# ConnS2.net
KiCad netlist of a schematic drawn in Altium Designer
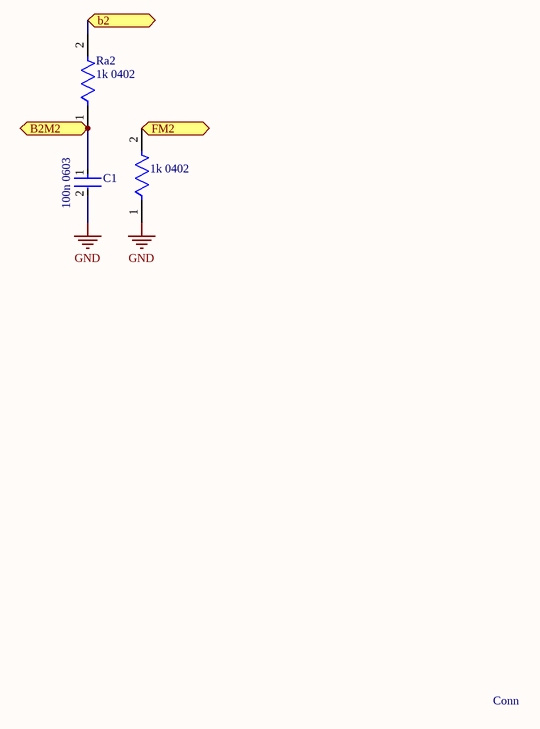
[diagram p0: ConnS2.SchDoc]

(export (version "E")
  (design (tool "Eeschema 10.0.6"))
  (components
    (comp (ref "C1")
      (value "100n 0603")
      (footprint "FP-C0603C-CF-MFG")
      (fields
        (field (name "MANUFACTURER PART NUMBER") "C0603C104K4RACTU")
        (field (name "OCTOPART") "https://octopart.com/c0603c104k4ractu-kemet-93067")
        (field (name "MANUFACTURER") "KEMET")
      )
      (libsource (lib "Altium Content Vault") (part "b4654b650e69147ec39a6b967a45e02"))
    )
    (comp (ref "Ra2")
      (value "1k 0402")
      (footprint "FP-CR0402-IPC_C")
      (description "Thick Film Chip Resistors 0402 1kΩ 0.0625W 1% 100ppm/°C")
      (fields (field (name "TOLERANCE") "1%"))
      (libsource (lib "Altium Content Vault") (part "1029c3af85768c4190bb7ad29bc67b5"))
    )
    (comp (ref "Rb2")
      (value "1k 0402")
      (footprint "FP-CR0402-IPC_C")
      (description "Thick Film Chip Resistors 0402 1kΩ 0.0625W 1% 100ppm/°C")
      (fields (field (name "TOLERANCE") "1%"))
      (libsource (lib "Altium Content Vault") (part "1029c3af85768c4190bb7ad29bc67b5"))
    )
  )
  (nets
    (net (code "1") (name "/B2M2") (class "Default")
      (node (ref "C1") (pin "1") (pinfunction "1_1") (pintype "passive"))
      (node (ref "Ra2") (pin "1") (pinfunction "1_1") (pintype "passive"))
    )
    (net (code "2") (name "/FM2") (class "Default")
      (node (ref "Rb2") (pin "2") (pinfunction "2_2") (pintype "passive"))
    )
    (net (code "3") (name "/b2") (class "Default")
      (node (ref "Ra2") (pin "2") (pinfunction "2_2") (pintype "passive"))
    )
    (net (code "4") (name "GND") (class "Default")
      (node (ref "C1") (pin "2") (pinfunction "2_2") (pintype "passive"))
      (node (ref "Rb2") (pin "1") (pinfunction "1_1") (pintype "passive"))
    )
  )
)
